# 07-EEPROM.net
KiCad netlist of a schematic drawn in Altium Designer
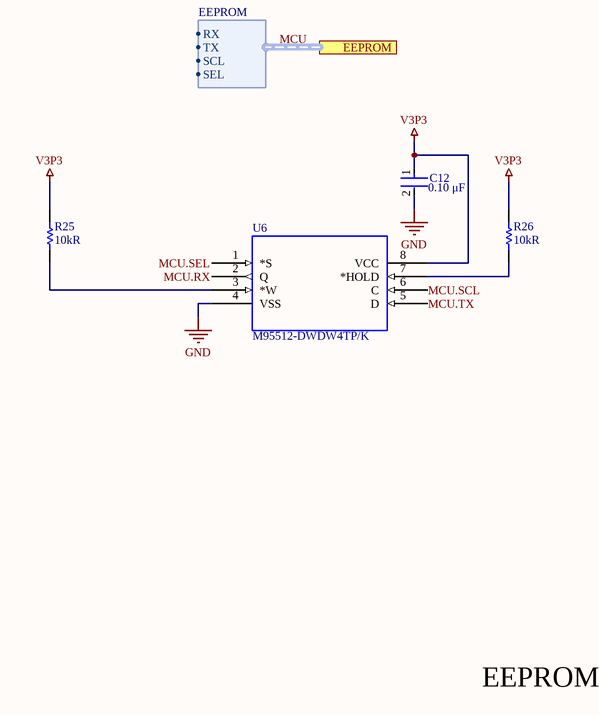
[diagram p0: 07-EEPROM.SchDoc]

(export (version "E")
  (design (tool "Eeschema 10.0.6"))
  (components
    (comp (ref "C12")
      (value "C0805C104K5RACTU")
      (footprint "FP-C0805C-DN-MFG")
      (description "CAP CER 0.1UF 50V X7R 0805")
      (fields
        (field (name "MANUFACTURER") "KEMET")
        (field (name "OCTOPART") "https://octopart.com/c0805c104k5ractu-kemet-143926")
        (field (name "CAPACITANCE") "0.10 μF")
      )
      (libsource (lib "Altium Content Vault") (part "b4654b650e69147ec39a6b967a45e02"))
    )
    (comp (ref "R25")
      (value "RC0805FR-0710KL")
      (footprint "RESC2013X60X35NL10T20")
      (description "Chip Resistor, 10 KOhm, +/- 1%, 0.125 W, -55 to 155 degC, 0805 (2012 Metric), RoHS, Tape and Reel")
      (fields
        (field (name "MANUFACTURER") "Yageo")
        (field (name "RESISTANCE") "10kR")
        (field (name "TOLERANCE") "1%")
      )
      (libsource (lib "Altium Content Vault") (part "RES-2"))
    )
    (comp (ref "R26")
      (value "RC0805FR-0710KL")
      (footprint "RESC2013X60X35NL10T20")
      (description "Chip Resistor, 10 KOhm, +/- 1%, 0.125 W, -55 to 155 degC, 0805 (2012 Metric), RoHS, Tape and Reel")
      (fields
        (field (name "MANUFACTURER") "Yageo")
        (field (name "RESISTANCE") "10kR")
        (field (name "TOLERANCE") "1%")
      )
      (libsource (lib "Altium Content Vault") (part "RES-2"))
    )
    (comp (ref "U6")
      (value "M95512-DWDW4TP/K")
      (footprint "TSSOP8_169MILS_DW_STM-M")
      (description "EEPROM Serial-SPI 512K-bit 64K x 8 3.3V/5V Automotive 8-Pin TSSOP T/R")
      (fields (field (name "COPYRIGHT") "Copyright (C) 2022 Ultra Librarian. All rights reserved."))
      (libsource (lib "uw-madison-parts") (part "M95512-DWDW4TP/K"))
    )
  )
  (nets
    (net (code "2") (name "/MCU.RX") (class "Default")
      (node (ref "U6") (pin "2") (pinfunction "Q_2") (pintype "output"))
    )
    (net (code "3") (name "/MCU.SCL") (class "Default")
      (node (ref "U6") (pin "6") (pinfunction "C_6") (pintype "input"))
    )
    (net (code "4") (name "/MCU.SEL") (class "Default")
      (node (ref "U6") (pin "1") (pinfunction "*S_1") (pintype "input"))
    )
    (net (code "5") (name "/MCU.TX") (class "Default")
      (node (ref "U6") (pin "5") (pinfunction "D_5") (pintype "input"))
    )
    (net (code "7") (name "GND") (class "Default")
      (node (ref "C12") (pin "2") (pinfunction "2_2") (pintype "passive"))
      (node (ref "U6") (pin "4") (pinfunction "VSS_4") (pintype "passive"))
    )
    (net (code "8") (name "Net-(U6-*HOLD)") (class "Default")
      (node (ref "R26") (pin "2") (pinfunction "2_2") (pintype "passive"))
      (node (ref "U6") (pin "7") (pinfunction "*HOLD_7") (pintype "input"))
    )
    (net (code "9") (name "Net-(U6-*W)") (class "Default")
      (node (ref "R25") (pin "2") (pinfunction "2_2") (pintype "passive"))
      (node (ref "U6") (pin "3") (pinfunction "*W_3") (pintype "input"))
    )
    (net (code "10") (name "V3P3") (class "Default")
      (node (ref "C12") (pin "1") (pinfunction "1_1") (pintype "passive"))
      (node (ref "R25") (pin "1") (pinfunction "1_1") (pintype "passive"))
      (node (ref "R26") (pin "1") (pinfunction "1_1") (pintype "passive"))
      (node (ref "U6") (pin "8") (pinfunction "VCC_8") (pintype "power_in"))
    )
  )
)
